# Sheet3.net
KiCad netlist of a schematic drawn in Altium Designer
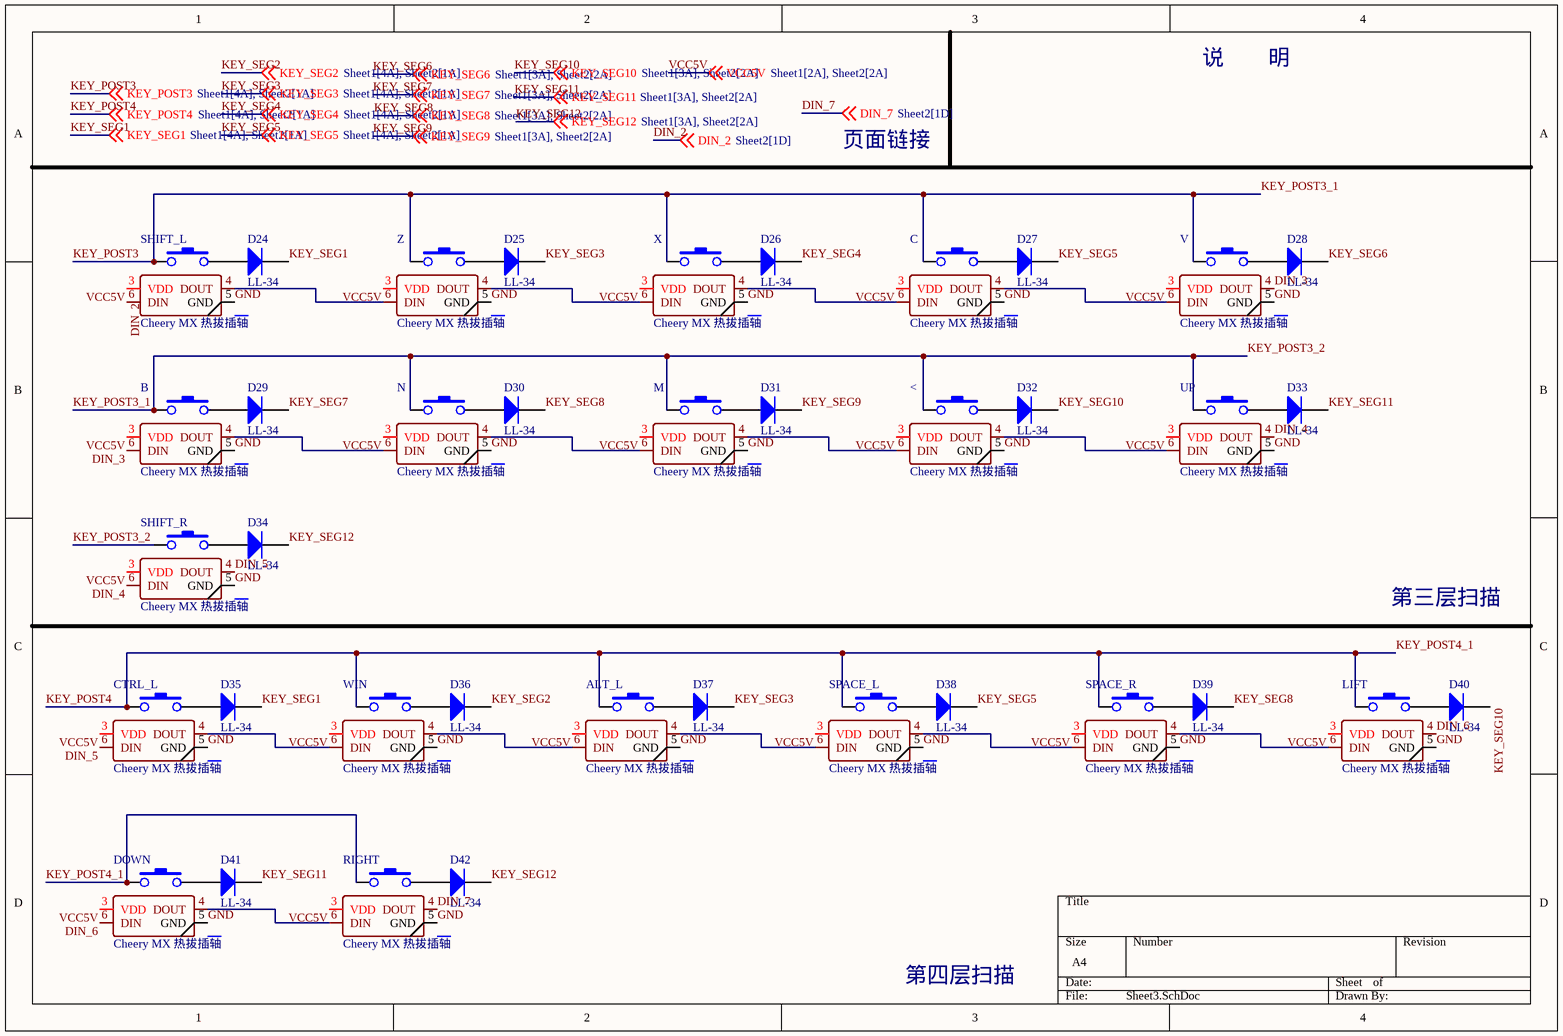
[diagram p0: Sheet3.SchDoc]

(export (version "E")
  (design (tool "Eeschema 10.0.6"))
  (components
    (comp (ref "<")
      (value "Cheery MX 热拔插轴")
      (footprint "MX_SW-HOTPLUG")
      (description "机械键盘轴（Cheery MX）")
      (libsource (lib "BaseLib") (part "Cheery MX 热拔插轴"))
    )
    (comp (ref "ALT_L")
      (value "Cheery MX 热拔插轴")
      (footprint "MX_SW-HOTPLUG")
      (description "机械键盘轴（Cheery MX）")
      (libsource (lib "BaseLib") (part "Cheery MX 热拔插轴"))
    )
    (comp (ref "B")
      (value "Cheery MX 热拔插轴")
      (footprint "MX_SW-HOTPLUG")
      (description "机械键盘轴（Cheery MX）")
      (libsource (lib "BaseLib") (part "Cheery MX 热拔插轴"))
    )
    (comp (ref "C")
      (value "Cheery MX 热拔插轴")
      (footprint "MX_SW-HOTPLUG")
      (description "机械键盘轴（Cheery MX）")
      (libsource (lib "BaseLib") (part "Cheery MX 热拔插轴"))
    )
    (comp (ref "CTRL_L")
      (value "Cheery MX 热拔插轴")
      (footprint "MX_SW-HOTPLUG")
      (description "机械键盘轴（Cheery MX）")
      (libsource (lib "BaseLib") (part "Cheery MX 热拔插轴"))
    )
    (comp (ref "D24")
      (value "LL-34")
      (footprint "LL-34_L3.7-W1.6-RD")
      (description "开关二极管（Switching diode）")
      (fields (field (name "PUBLISHER") "Altium Limited"))
      (libsource (lib "BaseLib") (part "LL4148"))
    )
    (comp (ref "D25")
      (value "LL-34")
      (footprint "LL-34_L3.7-W1.6-RD")
      (description "开关二极管（Switching diode）")
      (fields (field (name "PUBLISHER") "Altium Limited"))
      (libsource (lib "BaseLib") (part "LL4148"))
    )
    (comp (ref "D26")
      (value "LL-34")
      (footprint "LL-34_L3.7-W1.6-RD")
      (description "开关二极管（Switching diode）")
      (fields (field (name "PUBLISHER") "Altium Limited"))
      (libsource (lib "BaseLib") (part "LL4148"))
    )
    (comp (ref "D27")
      (value "LL-34")
      (footprint "LL-34_L3.7-W1.6-RD")
      (description "开关二极管（Switching diode）")
      (fields (field (name "PUBLISHER") "Altium Limited"))
      (libsource (lib "BaseLib") (part "LL4148"))
    )
    (comp (ref "D28")
      (value "LL-34")
      (footprint "LL-34_L3.7-W1.6-RD")
      (description "开关二极管（Switching diode）")
      (fields (field (name "PUBLISHER") "Altium Limited"))
      (libsource (lib "BaseLib") (part "LL4148"))
    )
    (comp (ref "D29")
      (value "LL-34")
      (footprint "LL-34_L3.7-W1.6-RD")
      (description "开关二极管（Switching diode）")
      (fields (field (name "PUBLISHER") "Altium Limited"))
      (libsource (lib "BaseLib") (part "LL4148"))
    )
    (comp (ref "D30")
      (value "LL-34")
      (footprint "LL-34_L3.7-W1.6-RD")
      (description "开关二极管（Switching diode）")
      (fields (field (name "PUBLISHER") "Altium Limited"))
      (libsource (lib "BaseLib") (part "LL4148"))
    )
    (comp (ref "D31")
      (value "LL-34")
      (footprint "LL-34_L3.7-W1.6-RD")
      (description "开关二极管（Switching diode）")
      (fields (field (name "PUBLISHER") "Altium Limited"))
      (libsource (lib "BaseLib") (part "LL4148"))
    )
    (comp (ref "D32")
      (value "LL-34")
      (footprint "LL-34_L3.7-W1.6-RD")
      (description "开关二极管（Switching diode）")
      (fields (field (name "PUBLISHER") "Altium Limited"))
      (libsource (lib "BaseLib") (part "LL4148"))
    )
    (comp (ref "D33")
      (value "LL-34")
      (footprint "LL-34_L3.7-W1.6-RD")
      (description "开关二极管（Switching diode）")
      (fields (field (name "PUBLISHER") "Altium Limited"))
      (libsource (lib "BaseLib") (part "LL4148"))
    )
    (comp (ref "D34")
      (value "LL-34")
      (footprint "LL-34_L3.7-W1.6-RD")
      (description "开关二极管（Switching diode）")
      (fields (field (name "PUBLISHER") "Altium Limited"))
      (libsource (lib "BaseLib") (part "LL4148"))
    )
    (comp (ref "D35")
      (value "LL-34")
      (footprint "LL-34_L3.7-W1.6-RD")
      (description "开关二极管（Switching diode）")
      (fields (field (name "PUBLISHER") "Altium Limited"))
      (libsource (lib "BaseLib") (part "LL4148"))
    )
    (comp (ref "D36")
      (value "LL-34")
      (footprint "LL-34_L3.7-W1.6-RD")
      (description "开关二极管（Switching diode）")
      (fields (field (name "PUBLISHER") "Altium Limited"))
      (libsource (lib "BaseLib") (part "LL4148"))
    )
    (comp (ref "D37")
      (value "LL-34")
      (footprint "LL-34_L3.7-W1.6-RD")
      (description "开关二极管（Switching diode）")
      (fields (field (name "PUBLISHER") "Altium Limited"))
      (libsource (lib "BaseLib") (part "LL4148"))
    )
    (comp (ref "D38")
      (value "LL-34")
      (footprint "LL-34_L3.7-W1.6-RD")
      (description "开关二极管（Switching diode）")
      (fields (field (name "PUBLISHER") "Altium Limited"))
      (libsource (lib "BaseLib") (part "LL4148"))
    )
    (comp (ref "D39")
      (value "LL-34")
      (footprint "LL-34_L3.7-W1.6-RD")
      (description "开关二极管（Switching diode）")
      (fields (field (name "PUBLISHER") "Altium Limited"))
      (libsource (lib "BaseLib") (part "LL4148"))
    )
    (comp (ref "D40")
      (value "LL-34")
      (footprint "LL-34_L3.7-W1.6-RD")
      (description "开关二极管（Switching diode）")
      (fields (field (name "PUBLISHER") "Altium Limited"))
      (libsource (lib "BaseLib") (part "LL4148"))
    )
    (comp (ref "D41")
      (value "LL-34")
      (footprint "LL-34_L3.7-W1.6-RD")
      (description "开关二极管（Switching diode）")
      (fields (field (name "PUBLISHER") "Altium Limited"))
      (libsource (lib "BaseLib") (part "LL4148"))
    )
    (comp (ref "D42")
      (value "LL-34")
      (footprint "LL-34_L3.7-W1.6-RD")
      (description "开关二极管（Switching diode）")
      (fields (field (name "PUBLISHER") "Altium Limited"))
      (libsource (lib "BaseLib") (part "LL4148"))
    )
    (comp (ref "DOWN")
      (value "Cheery MX 热拔插轴")
      (footprint "MX_SW-HOTPLUG")
      (description "机械键盘轴（Cheery MX）")
      (libsource (lib "BaseLib") (part "Cheery MX 热拔插轴"))
    )
    (comp (ref "LIFT")
      (value "Cheery MX 热拔插轴")
      (footprint "MX_SW-HOTPLUG")
      (description "机械键盘轴（Cheery MX）")
      (libsource (lib "BaseLib") (part "Cheery MX 热拔插轴"))
    )
    (comp (ref "M")
      (value "Cheery MX 热拔插轴")
      (footprint "MX_SW-HOTPLUG")
      (description "机械键盘轴（Cheery MX）")
      (libsource (lib "BaseLib") (part "Cheery MX 热拔插轴"))
    )
    (comp (ref "N")
      (value "Cheery MX 热拔插轴")
      (footprint "MX_SW-HOTPLUG")
      (description "机械键盘轴（Cheery MX）")
      (libsource (lib "BaseLib") (part "Cheery MX 热拔插轴"))
    )
    (comp (ref "RIGHT")
      (value "Cheery MX 热拔插轴")
      (footprint "MX_SW-HOTPLUG")
      (description "机械键盘轴（Cheery MX）")
      (libsource (lib "BaseLib") (part "Cheery MX 热拔插轴"))
    )
    (comp (ref "SHIFT_L")
      (value "Cheery MX 热拔插轴")
      (footprint "MX_SW-HOTPLUG")
      (description "机械键盘轴（Cheery MX）")
      (libsource (lib "BaseLib") (part "Cheery MX 热拔插轴"))
    )
    (comp (ref "SHIFT_R")
      (value "Cheery MX 热拔插轴")
      (footprint "MX_SW-HOTPLUG")
      (description "机械键盘轴（Cheery MX）")
      (libsource (lib "BaseLib") (part "Cheery MX 热拔插轴"))
    )
    (comp (ref "SPACE_L")
      (value "Cheery MX 热拔插轴")
      (footprint "MX_SW-HOTPLUG")
      (description "机械键盘轴（Cheery MX）")
      (libsource (lib "BaseLib") (part "Cheery MX 热拔插轴"))
    )
    (comp (ref "SPACE_R")
      (value "Cheery MX 热拔插轴")
      (footprint "MX_SW-HOTPLUG")
      (description "机械键盘轴（Cheery MX）")
      (libsource (lib "BaseLib") (part "Cheery MX 热拔插轴"))
    )
    (comp (ref "UP")
      (value "Cheery MX 热拔插轴")
      (footprint "MX_SW-HOTPLUG")
      (description "机械键盘轴（Cheery MX）")
      (libsource (lib "BaseLib") (part "Cheery MX 热拔插轴"))
    )
    (comp (ref "V")
      (value "Cheery MX 热拔插轴")
      (footprint "MX_SW-HOTPLUG")
      (description "机械键盘轴（Cheery MX）")
      (libsource (lib "BaseLib") (part "Cheery MX 热拔插轴"))
    )
    (comp (ref "WIN")
      (value "Cheery MX 热拔插轴")
      (footprint "MX_SW-HOTPLUG")
      (description "机械键盘轴（Cheery MX）")
      (libsource (lib "BaseLib") (part "Cheery MX 热拔插轴"))
    )
    (comp (ref "X")
      (value "Cheery MX 热拔插轴")
      (footprint "MX_SW-HOTPLUG")
      (description "机械键盘轴（Cheery MX）")
      (libsource (lib "BaseLib") (part "Cheery MX 热拔插轴"))
    )
    (comp (ref "Z")
      (value "Cheery MX 热拔插轴")
      (footprint "MX_SW-HOTPLUG")
      (description "机械键盘轴（Cheery MX）")
      (libsource (lib "BaseLib") (part "Cheery MX 热拔插轴"))
    )
  )
  (nets
    (net (code "1") (name "/DIN_3") (class "Default")
      (node (ref "B") (pin "6") (pinfunction "DIN_6") (pintype "passive"))
      (node (ref "V") (pin "4") (pinfunction "DOUT_4") (pintype "passive"))
    )
    (net (code "2") (name "/DIN_4") (class "Default")
      (node (ref "SHIFT_R") (pin "6") (pinfunction "DIN_6") (pintype "passive"))
      (node (ref "UP") (pin "4") (pinfunction "DOUT_4") (pintype "passive"))
    )
    (net (code "3") (name "/DIN_5") (class "Default")
      (node (ref "CTRL_L") (pin "6") (pinfunction "DIN_6") (pintype "passive"))
      (node (ref "SHIFT_R") (pin "4") (pinfunction "DOUT_4") (pintype "passive"))
    )
    (net (code "4") (name "/DIN_6") (class "Default")
      (node (ref "DOWN") (pin "6") (pinfunction "DIN_6") (pintype "passive"))
      (node (ref "LIFT") (pin "4") (pinfunction "DOUT_4") (pintype "passive"))
    )
    (net (code "5") (name "/GND") (class "Default")
      (node (ref "<") (pin "5") (pinfunction "GND_5") (pintype "passive"))
      (node (ref "ALT_L") (pin "5") (pinfunction "GND_5") (pintype "passive"))
      (node (ref "B") (pin "5") (pinfunction "GND_5") (pintype "passive"))
      (node (ref "C") (pin "5") (pinfunction "GND_5") (pintype "passive"))
      (node (ref "CTRL_L") (pin "5") (pinfunction "GND_5") (pintype "passive"))
      (node (ref "DOWN") (pin "5") (pinfunction "GND_5") (pintype "passive"))
      (node (ref "LIFT") (pin "5") (pinfunction "GND_5") (pintype "passive"))
      (node (ref "M") (pin "5") (pinfunction "GND_5") (pintype "passive"))
      (node (ref "N") (pin "5") (pinfunction "GND_5") (pintype "passive"))
      (node (ref "RIGHT") (pin "5") (pinfunction "GND_5") (pintype "passive"))
      (node (ref "SHIFT_L") (pin "5") (pinfunction "GND_5") (pintype "passive"))
      (node (ref "SHIFT_R") (pin "5") (pinfunction "GND_5") (pintype "passive"))
      (node (ref "SPACE_L") (pin "5") (pinfunction "GND_5") (pintype "passive"))
      (node (ref "SPACE_R") (pin "5") (pinfunction "GND_5") (pintype "passive"))
      (node (ref "UP") (pin "5") (pinfunction "GND_5") (pintype "passive"))
      (node (ref "V") (pin "5") (pinfunction "GND_5") (pintype "passive"))
      (node (ref "WIN") (pin "5") (pinfunction "GND_5") (pintype "passive"))
      (node (ref "X") (pin "5") (pinfunction "GND_5") (pintype "passive"))
      (node (ref "Z") (pin "5") (pinfunction "GND_5") (pintype "passive"))
    )
    (net (code "6") (name "DIN_2") (class "Default")
      (node (ref "SHIFT_L") (pin "6") (pinfunction "DIN_6") (pintype "passive"))
    )
    (net (code "7") (name "DIN_7") (class "Default")
      (node (ref "RIGHT") (pin "4") (pinfunction "DOUT_4") (pintype "passive"))
    )
    (net (code "8") (name "KEY_POST3") (class "Default")
      (node (ref "<") (pin "1") (pinfunction "1_1") (pintype "passive"))
      (node (ref "B") (pin "1") (pinfunction "1_1") (pintype "passive"))
      (node (ref "C") (pin "1") (pinfunction "1_1") (pintype "passive"))
      (node (ref "M") (pin "1") (pinfunction "1_1") (pintype "passive"))
      (node (ref "N") (pin "1") (pinfunction "1_1") (pintype "passive"))
      (node (ref "SHIFT_L") (pin "1") (pinfunction "1_1") (pintype "passive"))
      (node (ref "SHIFT_R") (pin "1") (pinfunction "1_1") (pintype "passive"))
      (node (ref "UP") (pin "1") (pinfunction "1_1") (pintype "passive"))
      (node (ref "V") (pin "1") (pinfunction "1_1") (pintype "passive"))
      (node (ref "X") (pin "1") (pinfunction "1_1") (pintype "passive"))
      (node (ref "Z") (pin "1") (pinfunction "1_1") (pintype "passive"))
    )
    (net (code "9") (name "KEY_POST4") (class "Default")
      (node (ref "ALT_L") (pin "1") (pinfunction "1_1") (pintype "passive"))
      (node (ref "CTRL_L") (pin "1") (pinfunction "1_1") (pintype "passive"))
      (node (ref "DOWN") (pin "1") (pinfunction "1_1") (pintype "passive"))
      (node (ref "LIFT") (pin "1") (pinfunction "1_1") (pintype "passive"))
      (node (ref "RIGHT") (pin "1") (pinfunction "1_1") (pintype "passive"))
      (node (ref "SPACE_L") (pin "1") (pinfunction "1_1") (pintype "passive"))
      (node (ref "SPACE_R") (pin "1") (pinfunction "1_1") (pintype "passive"))
      (node (ref "WIN") (pin "1") (pinfunction "1_1") (pintype "passive"))
    )
    (net (code "10") (name "KEY_SEG1") (class "Default")
      (node (ref "D24") (pin "2") (pinfunction "K_2") (pintype "passive"))
      (node (ref "D35") (pin "2") (pinfunction "K_2") (pintype "passive"))
    )
    (net (code "11") (name "KEY_SEG2") (class "Default")
      (node (ref "D36") (pin "2") (pinfunction "K_2") (pintype "passive"))
    )
    (net (code "12") (name "KEY_SEG3") (class "Default")
      (node (ref "D25") (pin "2") (pinfunction "K_2") (pintype "passive"))
      (node (ref "D37") (pin "2") (pinfunction "K_2") (pintype "passive"))
    )
    (net (code "13") (name "KEY_SEG4") (class "Default")
      (node (ref "D26") (pin "2") (pinfunction "K_2") (pintype "passive"))
    )
    (net (code "14") (name "KEY_SEG5") (class "Default")
      (node (ref "D27") (pin "2") (pinfunction "K_2") (pintype "passive"))
      (node (ref "D38") (pin "2") (pinfunction "K_2") (pintype "passive"))
    )
    (net (code "15") (name "KEY_SEG6") (class "Default")
      (node (ref "D28") (pin "2") (pinfunction "K_2") (pintype "passive"))
    )
    (net (code "16") (name "KEY_SEG7") (class "Default")
      (node (ref "D29") (pin "2") (pinfunction "K_2") (pintype "passive"))
    )
    (net (code "17") (name "KEY_SEG8") (class "Default")
      (node (ref "D30") (pin "2") (pinfunction "K_2") (pintype "passive"))
      (node (ref "D39") (pin "2") (pinfunction "K_2") (pintype "passive"))
    )
    (net (code "18") (name "KEY_SEG9") (class "Default")
      (node (ref "D31") (pin "2") (pinfunction "K_2") (pintype "passive"))
    )
    (net (code "19") (name "KEY_SEG10") (class "Default")
      (node (ref "D32") (pin "2") (pinfunction "K_2") (pintype "passive"))
      (node (ref "D40") (pin "2") (pinfunction "K_2") (pintype "passive"))
    )
    (net (code "20") (name "KEY_SEG11") (class "Default")
      (node (ref "D33") (pin "2") (pinfunction "K_2") (pintype "passive"))
      (node (ref "D41") (pin "2") (pinfunction "K_2") (pintype "passive"))
    )
    (net (code "21") (name "KEY_SEG12") (class "Default")
      (node (ref "D34") (pin "2") (pinfunction "K_2") (pintype "passive"))
      (node (ref "D42") (pin "2") (pinfunction "K_2") (pintype "passive"))
    )
    (net (code "22") (name "Net-(<-DIN)") (class "Default")
      (node (ref "<") (pin "6") (pinfunction "DIN_6") (pintype "passive"))
      (node (ref "M") (pin "4") (pinfunction "DOUT_4") (pintype "passive"))
    )
    (net (code "23") (name "Net-(<-DOUT)") (class "Default")
      (node (ref "<") (pin "4") (pinfunction "DOUT_4") (pintype "passive"))
      (node (ref "UP") (pin "6") (pinfunction "DIN_6") (pintype "passive"))
    )
    (net (code "24") (name "Net-(ALT_L-DIN)") (class "Default")
      (node (ref "ALT_L") (pin "6") (pinfunction "DIN_6") (pintype "passive"))
      (node (ref "WIN") (pin "4") (pinfunction "DOUT_4") (pintype "passive"))
    )
    (net (code "25") (name "Net-(ALT_L-DOUT)") (class "Default")
      (node (ref "ALT_L") (pin "4") (pinfunction "DOUT_4") (pintype "passive"))
      (node (ref "SPACE_L") (pin "6") (pinfunction "DIN_6") (pintype "passive"))
    )
    (net (code "26") (name "Net-(B-DOUT)") (class "Default")
      (node (ref "B") (pin "4") (pinfunction "DOUT_4") (pintype "passive"))
      (node (ref "N") (pin "6") (pinfunction "DIN_6") (pintype "passive"))
    )
    (net (code "27") (name "Net-(C-DIN)") (class "Default")
      (node (ref "C") (pin "6") (pinfunction "DIN_6") (pintype "passive"))
      (node (ref "X") (pin "4") (pinfunction "DOUT_4") (pintype "passive"))
    )
    (net (code "28") (name "Net-(C-DOUT)") (class "Default")
      (node (ref "C") (pin "4") (pinfunction "DOUT_4") (pintype "passive"))
      (node (ref "V") (pin "6") (pinfunction "DIN_6") (pintype "passive"))
    )
    (net (code "29") (name "Net-(CTRL_L-DOUT)") (class "Default")
      (node (ref "CTRL_L") (pin "4") (pinfunction "DOUT_4") (pintype "passive"))
      (node (ref "WIN") (pin "6") (pinfunction "DIN_6") (pintype "passive"))
    )
    (net (code "30") (name "Net-(D24-A)") (class "Default")
      (node (ref "D24") (pin "1") (pinfunction "A_1") (pintype "passive"))
      (node (ref "SHIFT_L") (pin "2") (pinfunction "2_2") (pintype "passive"))
    )
    (net (code "31") (name "Net-(D25-A)") (class "Default")
      (node (ref "D25") (pin "1") (pinfunction "A_1") (pintype "passive"))
      (node (ref "Z") (pin "2") (pinfunction "2_2") (pintype "passive"))
    )
    (net (code "32") (name "Net-(D26-A)") (class "Default")
      (node (ref "D26") (pin "1") (pinfunction "A_1") (pintype "passive"))
      (node (ref "X") (pin "2") (pinfunction "2_2") (pintype "passive"))
    )
    (net (code "33") (name "Net-(D27-A)") (class "Default")
      (node (ref "C") (pin "2") (pinfunction "2_2") (pintype "passive"))
      (node (ref "D27") (pin "1") (pinfunction "A_1") (pintype "passive"))
    )
    (net (code "34") (name "Net-(D28-A)") (class "Default")
      (node (ref "D28") (pin "1") (pinfunction "A_1") (pintype "passive"))
      (node (ref "V") (pin "2") (pinfunction "2_2") (pintype "passive"))
    )
    (net (code "35") (name "Net-(D29-A)") (class "Default")
      (node (ref "B") (pin "2") (pinfunction "2_2") (pintype "passive"))
      (node (ref "D29") (pin "1") (pinfunction "A_1") (pintype "passive"))
    )
    (net (code "36") (name "Net-(D30-A)") (class "Default")
      (node (ref "D30") (pin "1") (pinfunction "A_1") (pintype "passive"))
      (node (ref "N") (pin "2") (pinfunction "2_2") (pintype "passive"))
    )
    (net (code "37") (name "Net-(D31-A)") (class "Default")
      (node (ref "D31") (pin "1") (pinfunction "A_1") (pintype "passive"))
      (node (ref "M") (pin "2") (pinfunction "2_2") (pintype "passive"))
    )
    (net (code "38") (name "Net-(D32-A)") (class "Default")
      (node (ref "<") (pin "2") (pinfunction "2_2") (pintype "passive"))
      (node (ref "D32") (pin "1") (pinfunction "A_1") (pintype "passive"))
    )
    (net (code "39") (name "Net-(D33-A)") (class "Default")
      (node (ref "D33") (pin "1") (pinfunction "A_1") (pintype "passive"))
      (node (ref "UP") (pin "2") (pinfunction "2_2") (pintype "passive"))
    )
    (net (code "40") (name "Net-(D34-A)") (class "Default")
      (node (ref "D34") (pin "1") (pinfunction "A_1") (pintype "passive"))
      (node (ref "SHIFT_R") (pin "2") (pinfunction "2_2") (pintype "passive"))
    )
    (net (code "41") (name "Net-(D35-A)") (class "Default")
      (node (ref "CTRL_L") (pin "2") (pinfunction "2_2") (pintype "passive"))
      (node (ref "D35") (pin "1") (pinfunction "A_1") (pintype "passive"))
    )
    (net (code "42") (name "Net-(D36-A)") (class "Default")
      (node (ref "D36") (pin "1") (pinfunction "A_1") (pintype "passive"))
      (node (ref "WIN") (pin "2") (pinfunction "2_2") (pintype "passive"))
    )
    (net (code "43") (name "Net-(D37-A)") (class "Default")
      (node (ref "ALT_L") (pin "2") (pinfunction "2_2") (pintype "passive"))
      (node (ref "D37") (pin "1") (pinfunction "A_1") (pintype "passive"))
    )
    (net (code "44") (name "Net-(D38-A)") (class "Default")
      (node (ref "D38") (pin "1") (pinfunction "A_1") (pintype "passive"))
      (node (ref "SPACE_L") (pin "2") (pinfunction "2_2") (pintype "passive"))
    )
    (net (code "45") (name "Net-(D39-A)") (class "Default")
      (node (ref "D39") (pin "1") (pinfunction "A_1") (pintype "passive"))
      (node (ref "SPACE_R") (pin "2") (pinfunction "2_2") (pintype "passive"))
    )
    (net (code "46") (name "Net-(D40-A)") (class "Default")
      (node (ref "D40") (pin "1") (pinfunction "A_1") (pintype "passive"))
      (node (ref "LIFT") (pin "2") (pinfunction "2_2") (pintype "passive"))
    )
    (net (code "47") (name "Net-(D41-A)") (class "Default")
      (node (ref "D41") (pin "1") (pinfunction "A_1") (pintype "passive"))
      (node (ref "DOWN") (pin "2") (pinfunction "2_2") (pintype "passive"))
    )
    (net (code "48") (name "Net-(D42-A)") (class "Default")
      (node (ref "D42") (pin "1") (pinfunction "A_1") (pintype "passive"))
      (node (ref "RIGHT") (pin "2") (pinfunction "2_2") (pintype "passive"))
    )
    (net (code "49") (name "Net-(DOWN-DOUT)") (class "Default")
      (node (ref "DOWN") (pin "4") (pinfunction "DOUT_4") (pintype "passive"))
      (node (ref "RIGHT") (pin "6") (pinfunction "DIN_6") (pintype "passive"))
    )
    (net (code "50") (name "Net-(LIFT-DIN)") (class "Default")
      (node (ref "LIFT") (pin "6") (pinfunction "DIN_6") (pintype "passive"))
      (node (ref "SPACE_R") (pin "4") (pinfunction "DOUT_4") (pintype "passive"))
    )
    (net (code "51") (name "Net-(M-DIN)") (class "Default")
      (node (ref "M") (pin "6") (pinfunction "DIN_6") (pintype "passive"))
      (node (ref "N") (pin "4") (pinfunction "DOUT_4") (pintype "passive"))
    )
    (net (code "52") (name "Net-(SHIFT_L-DOUT)") (class "Default")
      (node (ref "SHIFT_L") (pin "4") (pinfunction "DOUT_4") (pintype "passive"))
      (node (ref "Z") (pin "6") (pinfunction "DIN_6") (pintype "passive"))
    )
    (net (code "53") (name "Net-(SPACE_L-DOUT)") (class "Default")
      (node (ref "SPACE_L") (pin "4") (pinfunction "DOUT_4") (pintype "passive"))
      (node (ref "SPACE_R") (pin "6") (pinfunction "DIN_6") (pintype "passive"))
    )
    (net (code "54") (name "Net-(X-DIN)") (class "Default")
      (node (ref "X") (pin "6") (pinfunction "DIN_6") (pintype "passive"))
      (node (ref "Z") (pin "4") (pinfunction "DOUT_4") (pintype "passive"))
    )
    (net (code "55") (name "VCC5V") (class "Default")
      (node (ref "<") (pin "3") (pinfunction "VDD_3") (pintype "passive"))
      (node (ref "ALT_L") (pin "3") (pinfunction "VDD_3") (pintype "passive"))
      (node (ref "B") (pin "3") (pinfunction "VDD_3") (pintype "passive"))
      (node (ref "C") (pin "3") (pinfunction "VDD_3") (pintype "passive"))
      (node (ref "CTRL_L") (pin "3") (pinfunction "VDD_3") (pintype "passive"))
      (node (ref "DOWN") (pin "3") (pinfunction "VDD_3") (pintype "passive"))
      (node (ref "LIFT") (pin "3") (pinfunction "VDD_3") (pintype "passive"))
      (node (ref "M") (pin "3") (pinfunction "VDD_3") (pintype "passive"))
      (node (ref "N") (pin "3") (pinfunction "VDD_3") (pintype "passive"))
      (node (ref "RIGHT") (pin "3") (pinfunction "VDD_3") (pintype "passive"))
      (node (ref "SHIFT_L") (pin "3") (pinfunction "VDD_3") (pintype "passive"))
      (node (ref "SHIFT_R") (pin "3") (pinfunction "VDD_3") (pintype "passive"))
      (node (ref "SPACE_L") (pin "3") (pinfunction "VDD_3") (pintype "passive"))
      (node (ref "SPACE_R") (pin "3") (pinfunction "VDD_3") (pintype "passive"))
      (node (ref "UP") (pin "3") (pinfunction "VDD_3") (pintype "passive"))
      (node (ref "V") (pin "3") (pinfunction "VDD_3") (pintype "passive"))
      (node (ref "WIN") (pin "3") (pinfunction "VDD_3") (pintype "passive"))
      (node (ref "X") (pin "3") (pinfunction "VDD_3") (pintype "passive"))
      (node (ref "Z") (pin "3") (pinfunction "VDD_3") (pintype "passive"))
    )
  )
)
